# output.net
KiCad netlist of a schematic drawn in EAGLE
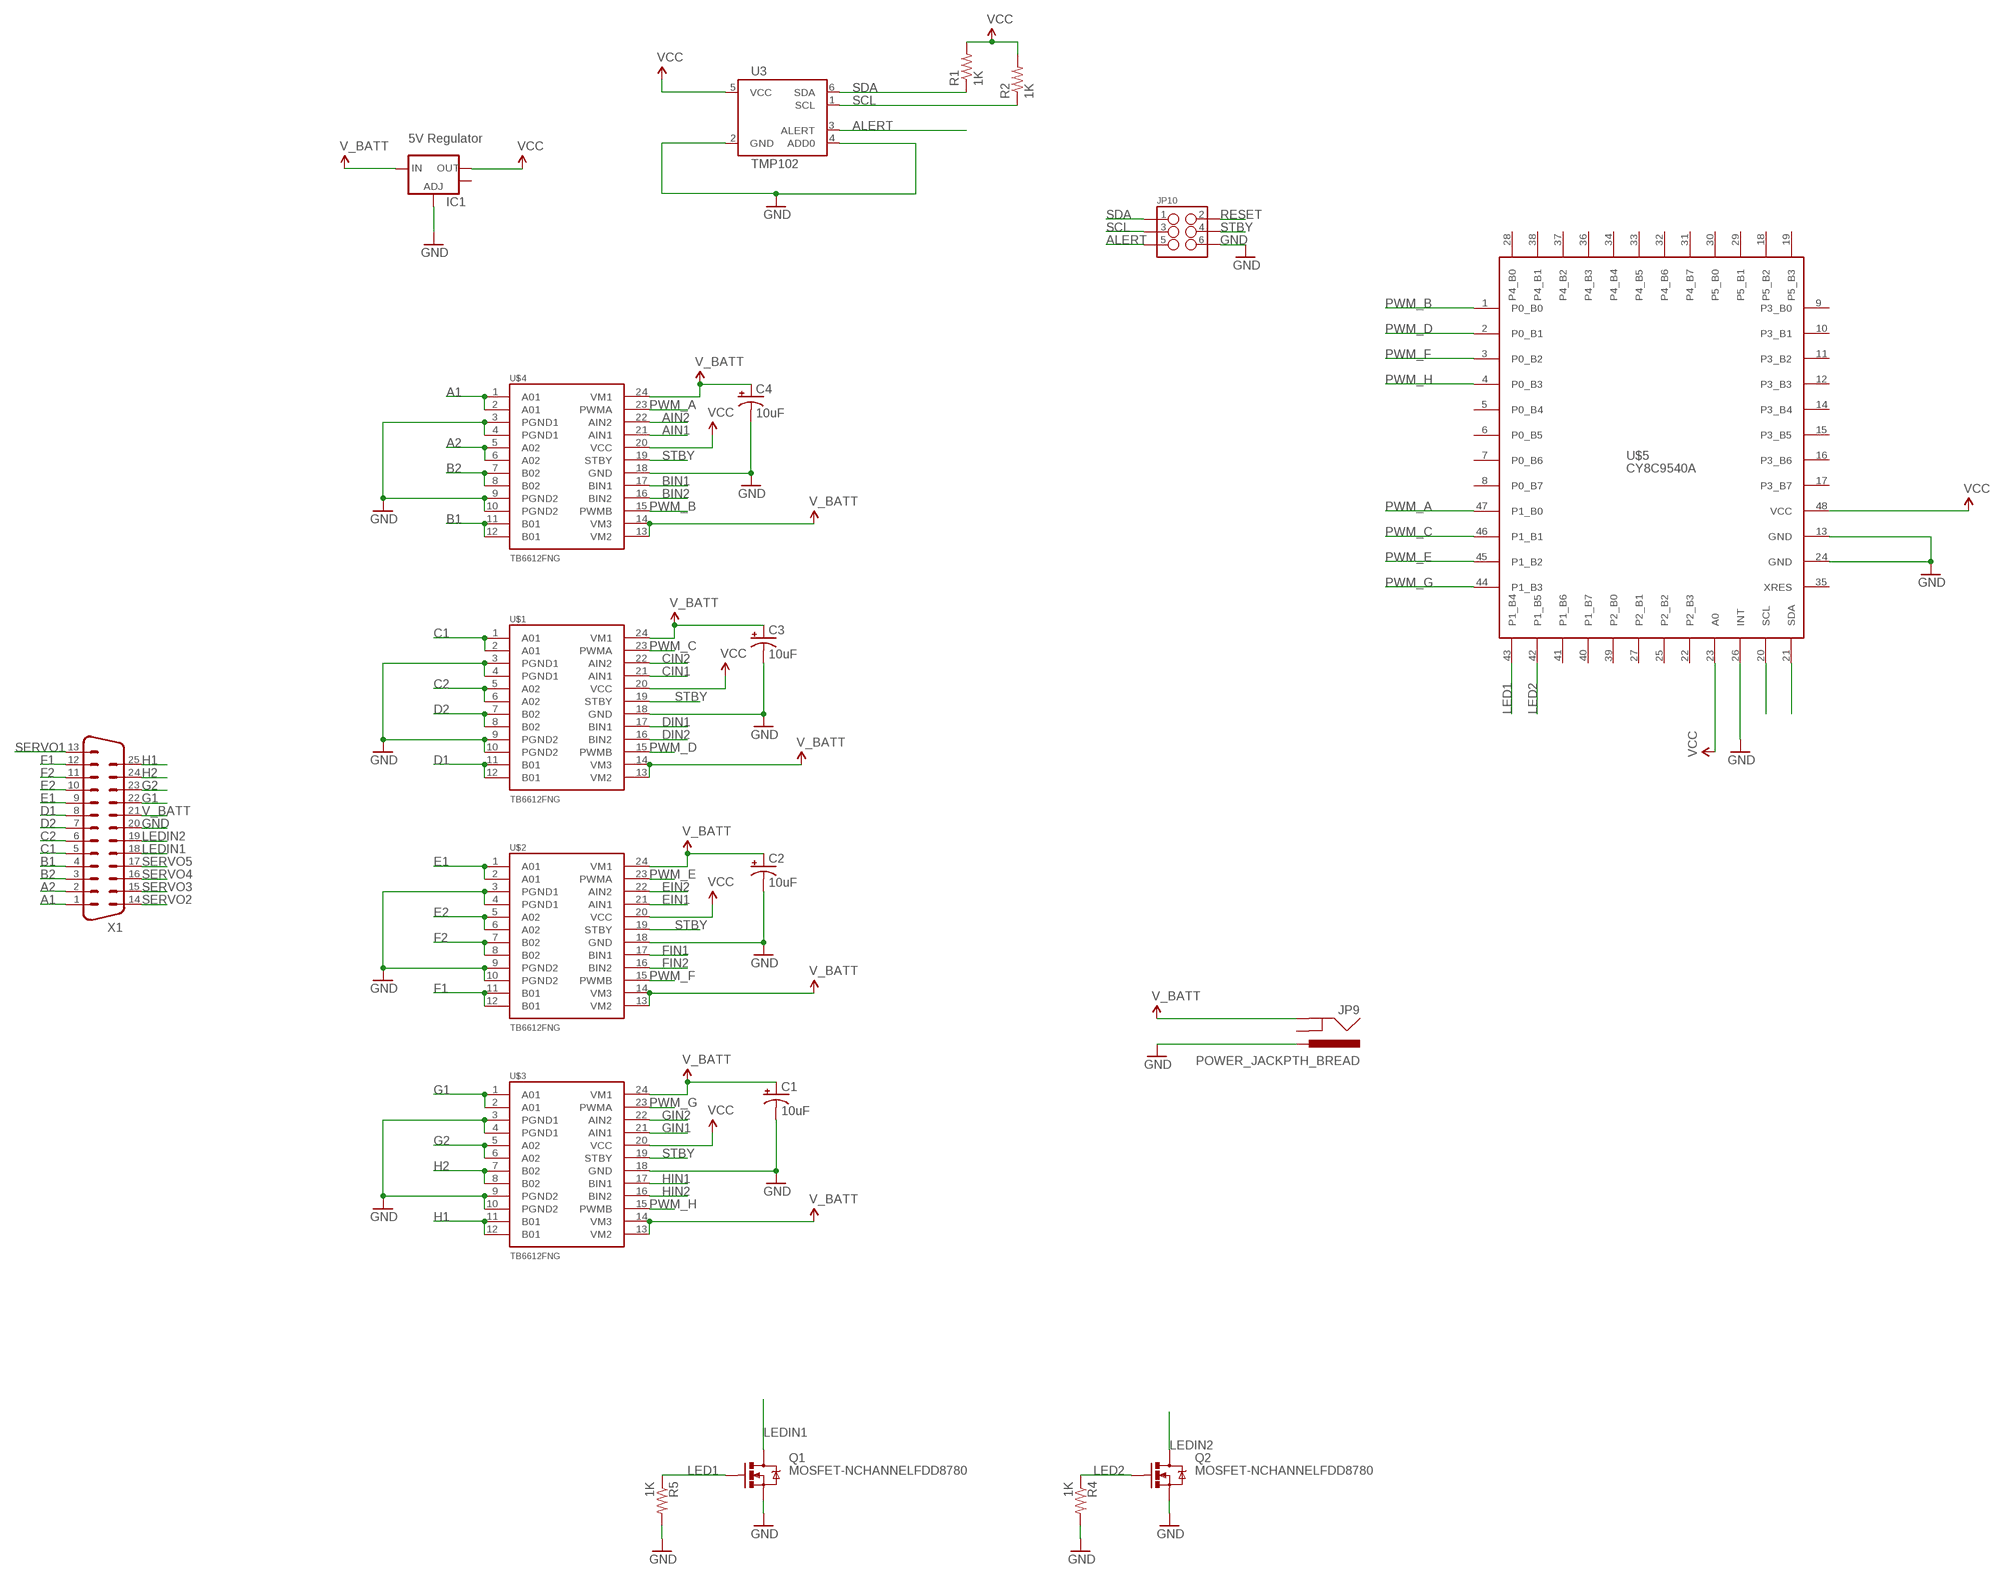
[diagram p0: schematic, sheet 1]

(export (version "E")
  (design (tool "Eeschema 10.0.6"))
  (components
    (comp (ref "C1")
      (value "10uF")
      (footprint "eagle-import:EIA3528")
      (libsource (lib "eagle-import") (part "10UF-20V-10%(TANT)"))
    )
    (comp (ref "C2")
      (value "10uF")
      (footprint "eagle-import:EIA3528")
      (libsource (lib "eagle-import") (part "10UF-20V-10%(TANT)"))
    )
    (comp (ref "C3")
      (value "10uF")
      (footprint "eagle-import:EIA3528")
      (libsource (lib "eagle-import") (part "10UF-20V-10%(TANT)"))
    )
    (comp (ref "C4")
      (value "10uF")
      (footprint "eagle-import:EIA3528")
      (libsource (lib "eagle-import") (part "10UF-20V-10%(TANT)"))
    )
    (comp (ref "IC1")
      (value "V_REG_LM1117SOT223")
      (footprint "eagle-import:SOT223")
      (libsource (lib "eagle-import") (part "V_REG_LM1117SOT223"))
    )
    (comp (ref "JP9")
      (value "POWER_JACKPTH_BREAD")
      (footprint "eagle-import:POWER_JACK_PTH_BREAD")
      (libsource (lib "eagle-import") (part "POWER_JACKPTH_BREAD"))
    )
    (comp (ref "JP10")
      (value "M03X2SHROUD")
      (footprint "eagle-import:2X3-SHROUDED")
      (libsource (lib "eagle-import") (part "M03X2SHROUD"))
    )
    (comp (ref "Q1")
      (value "MOSFET-NCHANNELFDD8780")
      (footprint "eagle-import:DPAK")
      (libsource (lib "eagle-import") (part "MOSFET-NCHANNELFDD8780"))
    )
    (comp (ref "Q2")
      (value "MOSFET-NCHANNELFDD8780")
      (footprint "eagle-import:DPAK")
      (libsource (lib "eagle-import") (part "MOSFET-NCHANNELFDD8780"))
    )
    (comp (ref "R1")
      (value "1K")
      (footprint "eagle-import:0603-RES")
      (libsource (lib "eagle-import") (part "1KOHM-1/10W-1%(0603)"))
    )
    (comp (ref "R2")
      (value "1K")
      (footprint "eagle-import:0603-RES")
      (libsource (lib "eagle-import") (part "1KOHM-1/10W-1%(0603)"))
    )
    (comp (ref "R4")
      (value "1K")
      (footprint "eagle-import:0603-RES")
      (libsource (lib "eagle-import") (part "1KOHM-1/10W-1%(0603)"))
    )
    (comp (ref "R5")
      (value "1K")
      (footprint "eagle-import:0603-RES")
      (libsource (lib "eagle-import") (part "1KOHM-1/10W-1%(0603)"))
    )
    (comp (ref "U$1")
      (value "TB6612FNG")
      (footprint "eagle-import:SSOP24")
      (libsource (lib "eagle-import") (part "TB6612FNG"))
    )
    (comp (ref "U$2")
      (value "TB6612FNG")
      (footprint "eagle-import:SSOP24")
      (libsource (lib "eagle-import") (part "TB6612FNG"))
    )
    (comp (ref "U$3")
      (value "TB6612FNG")
      (footprint "eagle-import:SSOP24")
      (libsource (lib "eagle-import") (part "TB6612FNG"))
    )
    (comp (ref "U$4")
      (value "TB6612FNG")
      (footprint "eagle-import:SSOP24")
      (libsource (lib "eagle-import") (part "TB6612FNG"))
    )
    (comp (ref "U$5")
      (value "CY8C9540A")
      (footprint "eagle-import:48-SSOP-CY")
      (libsource (lib "eagle-import") (part "CY8C9540A"))
    )
    (comp (ref "U3")
      (value "TMP102")
      (footprint "eagle-import:SOT563")
      (libsource (lib "eagle-import") (part "TMP102"))
    )
    (comp (ref "X1")
      (value "DB25D")
      (footprint "eagle-import:M25D")
      (libsource (lib "eagle-import") (part "DB25D"))
    )
  )
  (nets
    (net (code "1") (name "/A1") (class "Default")
      (node (ref "U$4") (pin "1") (pinfunction "A01_1") (pintype "bidirectional"))
      (node (ref "U$4") (pin "2") (pinfunction "A01_2") (pintype "bidirectional"))
      (node (ref "X1") (pin "1") (pinfunction "1_1") (pintype "passive"))
    )
    (net (code "2") (name "/A2") (class "Default")
      (node (ref "U$4") (pin "5") (pinfunction "A02_5") (pintype "bidirectional"))
      (node (ref "U$4") (pin "6") (pinfunction "A02_6") (pintype "bidirectional"))
      (node (ref "X1") (pin "2") (pinfunction "2_2") (pintype "passive"))
    )
    (net (code "3") (name "/AIN1") (class "Default")
      (node (ref "U$4") (pin "21") (pinfunction "AIN1_21") (pintype "bidirectional"))
    )
    (net (code "4") (name "/AIN2") (class "Default")
      (node (ref "U$4") (pin "22") (pinfunction "AIN2_22") (pintype "bidirectional"))
    )
    (net (code "5") (name "/ALERT") (class "Default")
      (node (ref "JP10") (pin "5") (pinfunction "5_5") (pintype "bidirectional"))
      (node (ref "U3") (pin "3") (pinfunction "ALERT_3") (pintype "bidirectional"))
    )
    (net (code "6") (name "/B1") (class "Default")
      (node (ref "U$4") (pin "11") (pinfunction "B01_11") (pintype "bidirectional"))
      (node (ref "U$4") (pin "12") (pinfunction "B01_12") (pintype "bidirectional"))
      (node (ref "X1") (pin "4") (pinfunction "4_4") (pintype "passive"))
    )
    (net (code "7") (name "/B2") (class "Default")
      (node (ref "U$4") (pin "7") (pinfunction "B02_7") (pintype "bidirectional"))
      (node (ref "U$4") (pin "8") (pinfunction "B02_8") (pintype "bidirectional"))
      (node (ref "X1") (pin "3") (pinfunction "3_3") (pintype "passive"))
    )
    (net (code "8") (name "/BIN1") (class "Default")
      (node (ref "U$4") (pin "17") (pinfunction "BIN1_17") (pintype "bidirectional"))
    )
    (net (code "9") (name "/BIN2") (class "Default")
      (node (ref "U$4") (pin "16") (pinfunction "BIN2_16") (pintype "bidirectional"))
    )
    (net (code "10") (name "/C1") (class "Default")
      (node (ref "U$1") (pin "1") (pinfunction "A01_1") (pintype "bidirectional"))
      (node (ref "U$1") (pin "2") (pinfunction "A01_2") (pintype "bidirectional"))
      (node (ref "X1") (pin "5") (pinfunction "5_5") (pintype "passive"))
    )
    (net (code "11") (name "/C2") (class "Default")
      (node (ref "U$1") (pin "5") (pinfunction "A02_5") (pintype "bidirectional"))
      (node (ref "U$1") (pin "6") (pinfunction "A02_6") (pintype "bidirectional"))
      (node (ref "X1") (pin "6") (pinfunction "6_6") (pintype "passive"))
    )
    (net (code "12") (name "/CIN1") (class "Default")
      (node (ref "U$1") (pin "21") (pinfunction "AIN1_21") (pintype "bidirectional"))
    )
    (net (code "13") (name "/CIN2") (class "Default")
      (node (ref "U$1") (pin "22") (pinfunction "AIN2_22") (pintype "bidirectional"))
    )
    (net (code "14") (name "/D1") (class "Default")
      (node (ref "U$1") (pin "11") (pinfunction "B01_11") (pintype "bidirectional"))
      (node (ref "U$1") (pin "12") (pinfunction "B01_12") (pintype "bidirectional"))
      (node (ref "X1") (pin "8") (pinfunction "8_8") (pintype "passive"))
    )
    (net (code "15") (name "/D2") (class "Default")
      (node (ref "U$1") (pin "7") (pinfunction "B02_7") (pintype "bidirectional"))
      (node (ref "U$1") (pin "8") (pinfunction "B02_8") (pintype "bidirectional"))
      (node (ref "X1") (pin "7") (pinfunction "7_7") (pintype "passive"))
    )
    (net (code "16") (name "/DIN1") (class "Default")
      (node (ref "U$1") (pin "17") (pinfunction "BIN1_17") (pintype "bidirectional"))
    )
    (net (code "17") (name "/DIN2") (class "Default")
      (node (ref "U$1") (pin "16") (pinfunction "BIN2_16") (pintype "bidirectional"))
    )
    (net (code "18") (name "/E1") (class "Default")
      (node (ref "U$2") (pin "1") (pinfunction "A01_1") (pintype "bidirectional"))
      (node (ref "U$2") (pin "2") (pinfunction "A01_2") (pintype "bidirectional"))
      (node (ref "X1") (pin "9") (pinfunction "9_9") (pintype "passive"))
    )
    (net (code "19") (name "/E2") (class "Default")
      (node (ref "U$2") (pin "5") (pinfunction "A02_5") (pintype "bidirectional"))
      (node (ref "U$2") (pin "6") (pinfunction "A02_6") (pintype "bidirectional"))
      (node (ref "X1") (pin "10") (pinfunction "10_10") (pintype "passive"))
    )
    (net (code "20") (name "/EIN1") (class "Default")
      (node (ref "U$2") (pin "21") (pinfunction "AIN1_21") (pintype "bidirectional"))
    )
    (net (code "21") (name "/EIN2") (class "Default")
      (node (ref "U$2") (pin "22") (pinfunction "AIN2_22") (pintype "bidirectional"))
    )
    (net (code "22") (name "/F1") (class "Default")
      (node (ref "U$2") (pin "11") (pinfunction "B01_11") (pintype "bidirectional"))
      (node (ref "U$2") (pin "12") (pinfunction "B01_12") (pintype "bidirectional"))
      (node (ref "X1") (pin "12") (pinfunction "12_12") (pintype "passive"))
    )
    (net (code "23") (name "/F2") (class "Default")
      (node (ref "U$2") (pin "7") (pinfunction "B02_7") (pintype "bidirectional"))
      (node (ref "U$2") (pin "8") (pinfunction "B02_8") (pintype "bidirectional"))
      (node (ref "X1") (pin "11") (pinfunction "11_11") (pintype "passive"))
    )
    (net (code "24") (name "/FIN1") (class "Default")
      (node (ref "U$2") (pin "17") (pinfunction "BIN1_17") (pintype "bidirectional"))
    )
    (net (code "25") (name "/FIN2") (class "Default")
      (node (ref "U$2") (pin "16") (pinfunction "BIN2_16") (pintype "bidirectional"))
    )
    (net (code "26") (name "/G1") (class "Default")
      (node (ref "U$3") (pin "1") (pinfunction "A01_1") (pintype "bidirectional"))
      (node (ref "U$3") (pin "2") (pinfunction "A01_2") (pintype "bidirectional"))
      (node (ref "X1") (pin "22") (pinfunction "22_22") (pintype "passive"))
    )
    (net (code "27") (name "/G2") (class "Default")
      (node (ref "U$3") (pin "5") (pinfunction "A02_5") (pintype "bidirectional"))
      (node (ref "U$3") (pin "6") (pinfunction "A02_6") (pintype "bidirectional"))
      (node (ref "X1") (pin "23") (pinfunction "23_23") (pintype "passive"))
    )
    (net (code "28") (name "/GIN1") (class "Default")
      (node (ref "U$3") (pin "21") (pinfunction "AIN1_21") (pintype "bidirectional"))
    )
    (net (code "29") (name "/GIN2") (class "Default")
      (node (ref "U$3") (pin "22") (pinfunction "AIN2_22") (pintype "bidirectional"))
    )
    (net (code "30") (name "/H1") (class "Default")
      (node (ref "U$3") (pin "11") (pinfunction "B01_11") (pintype "bidirectional"))
      (node (ref "U$3") (pin "12") (pinfunction "B01_12") (pintype "bidirectional"))
      (node (ref "X1") (pin "25") (pinfunction "25_25") (pintype "passive"))
    )
    (net (code "31") (name "/H2") (class "Default")
      (node (ref "U$3") (pin "7") (pinfunction "B02_7") (pintype "bidirectional"))
      (node (ref "U$3") (pin "8") (pinfunction "B02_8") (pintype "bidirectional"))
      (node (ref "X1") (pin "24") (pinfunction "24_24") (pintype "passive"))
    )
    (net (code "32") (name "/HIN1") (class "Default")
      (node (ref "U$3") (pin "17") (pinfunction "BIN1_17") (pintype "bidirectional"))
    )
    (net (code "33") (name "/HIN2") (class "Default")
      (node (ref "U$3") (pin "16") (pinfunction "BIN2_16") (pintype "bidirectional"))
    )
    (net (code "34") (name "/LED1") (class "Default")
      (node (ref "Q1") (pin "1") (pinfunction "G_1") (pintype "passive"))
      (node (ref "R5") (pin "1") (pinfunction "1_1") (pintype "passive"))
      (node (ref "U$5") (pin "43") (pinfunction "P1_B4_43") (pintype "bidirectional"))
    )
    (net (code "35") (name "/LED2") (class "Default")
      (node (ref "Q2") (pin "1") (pinfunction "G_1") (pintype "passive"))
      (node (ref "R4") (pin "1") (pinfunction "1_1") (pintype "passive"))
      (node (ref "U$5") (pin "42") (pinfunction "P1_B5_42") (pintype "bidirectional"))
    )
    (net (code "36") (name "/LEDIN1") (class "Default")
      (node (ref "Q1") (pin "4") (pinfunction "D_4") (pintype "passive"))
      (node (ref "X1") (pin "18") (pinfunction "18_18") (pintype "passive"))
    )
    (net (code "37") (name "/LEDIN2") (class "Default")
      (node (ref "Q2") (pin "4") (pinfunction "D_4") (pintype "passive"))
      (node (ref "X1") (pin "19") (pinfunction "19_19") (pintype "passive"))
    )
    (net (code "38") (name "/PWM_A") (class "Default")
      (node (ref "U$4") (pin "23") (pinfunction "PWMA_23") (pintype "bidirectional"))
      (node (ref "U$5") (pin "47") (pinfunction "P1_B0_47") (pintype "bidirectional"))
    )
    (net (code "39") (name "/PWM_B") (class "Default")
      (node (ref "U$4") (pin "15") (pinfunction "PWMB_15") (pintype "bidirectional"))
      (node (ref "U$5") (pin "1") (pinfunction "P0_B0_1") (pintype "bidirectional"))
    )
    (net (code "40") (name "/PWM_C") (class "Default")
      (node (ref "U$1") (pin "23") (pinfunction "PWMA_23") (pintype "bidirectional"))
      (node (ref "U$5") (pin "46") (pinfunction "P1_B1_46") (pintype "bidirectional"))
    )
    (net (code "41") (name "/PWM_D") (class "Default")
      (node (ref "U$1") (pin "15") (pinfunction "PWMB_15") (pintype "bidirectional"))
      (node (ref "U$5") (pin "2") (pinfunction "P0_B1_2") (pintype "bidirectional"))
    )
    (net (code "42") (name "/PWM_E") (class "Default")
      (node (ref "U$2") (pin "23") (pinfunction "PWMA_23") (pintype "bidirectional"))
      (node (ref "U$5") (pin "45") (pinfunction "P1_B2_45") (pintype "bidirectional"))
    )
    (net (code "43") (name "/PWM_F") (class "Default")
      (node (ref "U$2") (pin "15") (pinfunction "PWMB_15") (pintype "bidirectional"))
      (node (ref "U$5") (pin "3") (pinfunction "P0_B2_3") (pintype "bidirectional"))
    )
    (net (code "44") (name "/PWM_G") (class "Default")
      (node (ref "U$3") (pin "23") (pinfunction "PWMA_23") (pintype "bidirectional"))
      (node (ref "U$5") (pin "44") (pinfunction "P1_B3_44") (pintype "bidirectional"))
    )
    (net (code "45") (name "/PWM_H") (class "Default")
      (node (ref "U$3") (pin "15") (pinfunction "PWMB_15") (pintype "bidirectional"))
      (node (ref "U$5") (pin "4") (pinfunction "P0_B3_4") (pintype "bidirectional"))
    )
    (net (code "46") (name "/RESET") (class "Default")
      (node (ref "JP10") (pin "2") (pinfunction "2_2") (pintype "bidirectional"))
    )
    (net (code "47") (name "/SCL") (class "Default")
      (node (ref "JP10") (pin "3") (pinfunction "3_3") (pintype "bidirectional"))
      (node (ref "R2") (pin "1") (pinfunction "1_1") (pintype "passive"))
      (node (ref "U$5") (pin "20") (pinfunction "SCL_20") (pintype "bidirectional"))
      (node (ref "U3") (pin "1") (pinfunction "SCL_1") (pintype "bidirectional"))
    )
    (net (code "48") (name "/SDA") (class "Default")
      (node (ref "JP10") (pin "1") (pinfunction "1_1") (pintype "bidirectional"))
      (node (ref "R1") (pin "1") (pinfunction "1_1") (pintype "passive"))
      (node (ref "U$5") (pin "21") (pinfunction "SDA_21") (pintype "bidirectional"))
      (node (ref "U3") (pin "6") (pinfunction "SDA_6") (pintype "bidirectional"))
    )
    (net (code "49") (name "/SERVO1") (class "Default")
      (node (ref "X1") (pin "13") (pinfunction "13_13") (pintype "passive"))
    )
    (net (code "50") (name "/SERVO2") (class "Default")
      (node (ref "X1") (pin "14") (pinfunction "14_14") (pintype "passive"))
    )
    (net (code "51") (name "/SERVO3") (class "Default")
      (node (ref "X1") (pin "15") (pinfunction "15_15") (pintype "passive"))
    )
    (net (code "52") (name "/SERVO4") (class "Default")
      (node (ref "X1") (pin "16") (pinfunction "16_16") (pintype "passive"))
    )
    (net (code "53") (name "/SERVO5") (class "Default")
      (node (ref "X1") (pin "17") (pinfunction "17_17") (pintype "passive"))
    )
    (net (code "54") (name "/STBY") (class "Default")
      (node (ref "JP10") (pin "4") (pinfunction "4_4") (pintype "bidirectional"))
      (node (ref "U$1") (pin "19") (pinfunction "STBY_19") (pintype "bidirectional"))
      (node (ref "U$2") (pin "19") (pinfunction "STBY_19") (pintype "bidirectional"))
      (node (ref "U$3") (pin "19") (pinfunction "STBY_19") (pintype "bidirectional"))
      (node (ref "U$4") (pin "19") (pinfunction "STBY_19") (pintype "bidirectional"))
    )
    (net (code "55") (name "GND") (class "Default")
      (node (ref "C1") (pin "C") (pinfunction "-_C") (pintype "passive"))
      (node (ref "C2") (pin "C") (pinfunction "-_C") (pintype "passive"))
      (node (ref "C3") (pin "C") (pinfunction "-_C") (pintype "passive"))
      (node (ref "C4") (pin "C") (pinfunction "-_C") (pintype "passive"))
      (node (ref "IC1") (pin "1") (pinfunction "ADJ_1") (pintype "input"))
      (node (ref "JP10") (pin "6") (pinfunction "6_6") (pintype "bidirectional"))
      (node (ref "JP9") (pin "PWR") (pinfunction "PWR_PWR") (pintype "bidirectional"))
      (node (ref "Q1") (pin "3") (pinfunction "S_3") (pintype "passive"))
      (node (ref "Q2") (pin "3") (pinfunction "S_3") (pintype "passive"))
      (node (ref "R4") (pin "2") (pinfunction "2_2") (pintype "passive"))
      (node (ref "R5") (pin "2") (pinfunction "2_2") (pintype "passive"))
      (node (ref "U$1") (pin "10") (pinfunction "PGND2_10") (pintype "bidirectional"))
      (node (ref "U$1") (pin "18") (pinfunction "GND_18") (pintype "bidirectional"))
      (node (ref "U$1") (pin "3") (pinfunction "PGND1_3") (pintype "bidirectional"))
      (node (ref "U$1") (pin "4") (pinfunction "PGND1_4") (pintype "bidirectional"))
      (node (ref "U$1") (pin "9") (pinfunction "PGND2_9") (pintype "bidirectional"))
      (node (ref "U$2") (pin "10") (pinfunction "PGND2_10") (pintype "bidirectional"))
      (node (ref "U$2") (pin "18") (pinfunction "GND_18") (pintype "bidirectional"))
      (node (ref "U$2") (pin "3") (pinfunction "PGND1_3") (pintype "bidirectional"))
      (node (ref "U$2") (pin "4") (pinfunction "PGND1_4") (pintype "bidirectional"))
      (node (ref "U$2") (pin "9") (pinfunction "PGND2_9") (pintype "bidirectional"))
      (node (ref "U$3") (pin "10") (pinfunction "PGND2_10") (pintype "bidirectional"))
      (node (ref "U$3") (pin "18") (pinfunction "GND_18") (pintype "bidirectional"))
      (node (ref "U$3") (pin "3") (pinfunction "PGND1_3") (pintype "bidirectional"))
      (node (ref "U$3") (pin "4") (pinfunction "PGND1_4") (pintype "bidirectional"))
      (node (ref "U$3") (pin "9") (pinfunction "PGND2_9") (pintype "bidirectional"))
      (node (ref "U$4") (pin "10") (pinfunction "PGND2_10") (pintype "bidirectional"))
      (node (ref "U$4") (pin "18") (pinfunction "GND_18") (pintype "bidirectional"))
      (node (ref "U$4") (pin "3") (pinfunction "PGND1_3") (pintype "bidirectional"))
      (node (ref "U$4") (pin "4") (pinfunction "PGND1_4") (pintype "bidirectional"))
      (node (ref "U$4") (pin "9") (pinfunction "PGND2_9") (pintype "bidirectional"))
      (node (ref "U$5") (pin "13") (pinfunction "GND_13") (pintype "bidirectional"))
      (node (ref "U$5") (pin "24") (pinfunction "GND_24") (pintype "bidirectional"))
      (node (ref "U$5") (pin "26") (pinfunction "INT_26") (pintype "bidirectional"))
      (node (ref "U3") (pin "2") (pinfunction "GND_2") (pintype "bidirectional"))
      (node (ref "U3") (pin "4") (pinfunction "ADD0_4") (pintype "bidirectional"))
      (node (ref "X1") (pin "20") (pinfunction "20_20") (pintype "passive"))
    )
    (net (code "56") (name "VCC") (class "Default")
      (node (ref "IC1") (pin "2") (pinfunction "OUT_2") (pintype "output"))
      (node (ref "R1") (pin "2") (pinfunction "2_2") (pintype "passive"))
      (node (ref "R2") (pin "2") (pinfunction "2_2") (pintype "passive"))
      (node (ref "U$1") (pin "20") (pinfunction "VCC_20") (pintype "bidirectional"))
      (node (ref "U$2") (pin "20") (pinfunction "VCC_20") (pintype "bidirectional"))
      (node (ref "U$3") (pin "20") (pinfunction "VCC_20") (pintype "bidirectional"))
      (node (ref "U$4") (pin "20") (pinfunction "VCC_20") (pintype "bidirectional"))
      (node (ref "U$5") (pin "23") (pinfunction "A0_23") (pintype "bidirectional"))
      (node (ref "U$5") (pin "48") (pinfunction "VCC_48") (pintype "bidirectional"))
      (node (ref "U3") (pin "5") (pinfunction "VCC_5") (pintype "bidirectional"))
    )
    (net (code "57") (name "V_BATT") (class "Default")
      (node (ref "C1") (pin "A") (pinfunction "+_A") (pintype "passive"))
      (node (ref "C2") (pin "A") (pinfunction "+_A") (pintype "passive"))
      (node (ref "C3") (pin "A") (pinfunction "+_A") (pintype "passive"))
      (node (ref "C4") (pin "A") (pinfunction "+_A") (pintype "passive"))
      (node (ref "IC1") (pin "3") (pinfunction "IN_3") (pintype "input"))
      (node (ref "JP9") (pin "GND") (pinfunction "GND_GND") (pintype "bidirectional"))
      (node (ref "U$1") (pin "13") (pinfunction "VM2_13") (pintype "bidirectional"))
      (node (ref "U$1") (pin "14") (pinfunction "VM3_14") (pintype "bidirectional"))
      (node (ref "U$1") (pin "24") (pinfunction "VM1_24") (pintype "bidirectional"))
      (node (ref "U$2") (pin "13") (pinfunction "VM2_13") (pintype "bidirectional"))
      (node (ref "U$2") (pin "14") (pinfunction "VM3_14") (pintype "bidirectional"))
      (node (ref "U$2") (pin "24") (pinfunction "VM1_24") (pintype "bidirectional"))
      (node (ref "U$3") (pin "13") (pinfunction "VM2_13") (pintype "bidirectional"))
      (node (ref "U$3") (pin "14") (pinfunction "VM3_14") (pintype "bidirectional"))
      (node (ref "U$3") (pin "24") (pinfunction "VM1_24") (pintype "bidirectional"))
      (node (ref "U$4") (pin "13") (pinfunction "VM2_13") (pintype "bidirectional"))
      (node (ref "U$4") (pin "14") (pinfunction "VM3_14") (pintype "bidirectional"))
      (node (ref "U$4") (pin "24") (pinfunction "VM1_24") (pintype "bidirectional"))
      (node (ref "X1") (pin "21") (pinfunction "21_21") (pintype "passive"))
    )
    (net (code "58") (name "unconnected-(IC1-OUT-Pad4)") (class "Default")
      (node (ref "IC1") (pin "4") (pinfunction "OUT_4") (pintype "output"))
    )
    (net (code "59") (name "unconnected-(JP9-PadGNDBREAK)") (class "Default")
      (node (ref "JP9") (pin "GNDBREAK") (pinfunction "GNDBREAK_GNDBREAK") (pintype "bidirectional"))
    )
    (net (code "60") (name "unconnected-(U$5-P0_B4-Pad5)") (class "Default")
      (node (ref "U$5") (pin "5") (pinfunction "P0_B4_5") (pintype "bidirectional"))
    )
    (net (code "61") (name "unconnected-(U$5-P0_B5-Pad6)") (class "Default")
      (node (ref "U$5") (pin "6") (pinfunction "P0_B5_6") (pintype "bidirectional"))
    )
    (net (code "62") (name "unconnected-(U$5-P0_B6-Pad7)") (class "Default")
      (node (ref "U$5") (pin "7") (pinfunction "P0_B6_7") (pintype "bidirectional"))
    )
    (net (code "63") (name "unconnected-(U$5-P0_B7-Pad8)") (class "Default")
      (node (ref "U$5") (pin "8") (pinfunction "P0_B7_8") (pintype "bidirectional"))
    )
    (net (code "64") (name "unconnected-(U$5-P1_B6-Pad41)") (class "Default")
      (node (ref "U$5") (pin "41") (pinfunction "P1_B6_41") (pintype "bidirectional"))
    )
    (net (code "65") (name "unconnected-(U$5-P1_B7-Pad40)") (class "Default")
      (node (ref "U$5") (pin "40") (pinfunction "P1_B7_40") (pintype "bidirectional"))
    )
    (net (code "66") (name "unconnected-(U$5-P2_B0-Pad39)") (class "Default")
      (node (ref "U$5") (pin "39") (pinfunction "P2_B0_39") (pintype "bidirectional"))
    )
    (net (code "67") (name "unconnected-(U$5-P2_B1-Pad27)") (class "Default")
      (node (ref "U$5") (pin "27") (pinfunction "P2_B1_27") (pintype "bidirectional"))
    )
    (net (code "68") (name "unconnected-(U$5-P2_B2-Pad25)") (class "Default")
      (node (ref "U$5") (pin "25") (pinfunction "P2_B2_25") (pintype "bidirectional"))
    )
    (net (code "69") (name "unconnected-(U$5-P2_B3-Pad22)") (class "Default")
      (node (ref "U$5") (pin "22") (pinfunction "P2_B3_22") (pintype "bidirectional"))
    )
    (net (code "70") (name "unconnected-(U$5-P3_B0-Pad9)") (class "Default")
      (node (ref "U$5") (pin "9") (pinfunction "P3_B0_9") (pintype "bidirectional"))
    )
    (net (code "71") (name "unconnected-(U$5-P3_B1-Pad10)") (class "Default")
      (node (ref "U$5") (pin "10") (pinfunction "P3_B1_10") (pintype "bidirectional"))
    )
    (net (code "72") (name "unconnected-(U$5-P3_B2-Pad11)") (class "Default")
      (node (ref "U$5") (pin "11") (pinfunction "P3_B2_11") (pintype "bidirectional"))
    )
    (net (code "73") (name "unconnected-(U$5-P3_B3-Pad12)") (class "Default")
      (node (ref "U$5") (pin "12") (pinfunction "P3_B3_12") (pintype "bidirectional"))
    )
    (net (code "74") (name "unconnected-(U$5-P3_B4-Pad14)") (class "Default")
      (node (ref "U$5") (pin "14") (pinfunction "P3_B4_14") (pintype "bidirectional"))
    )
    (net (code "75") (name "unconnected-(U$5-P3_B5-Pad15)") (class "Default")
      (node (ref "U$5") (pin "15") (pinfunction "P3_B5_15") (pintype "bidirectional"))
    )
    (net (code "76") (name "unconnected-(U$5-P3_B6-Pad16)") (class "Default")
      (node (ref "U$5") (pin "16") (pinfunction "P3_B6_16") (pintype "bidirectional"))
    )
    (net (code "77") (name "unconnected-(U$5-P3_B7-Pad17)") (class "Default")
      (node (ref "U$5") (pin "17") (pinfunction "P3_B7_17") (pintype "bidirectional"))
    )
    (net (code "78") (name "unconnected-(U$5-P4_B0-Pad28)") (class "Default")
      (node (ref "U$5") (pin "28") (pinfunction "P4_B0_28") (pintype "bidirectional"))
    )
    (net (code "79") (name "unconnected-(U$5-P4_B1-Pad38)") (class "Default")
      (node (ref "U$5") (pin "38") (pinfunction "P4_B1_38") (pintype "bidirectional"))
    )
    (net (code "80") (name "unconnected-(U$5-P4_B2-Pad37)") (class "Default")
      (node (ref "U$5") (pin "37") (pinfunction "P4_B2_37") (pintype "bidirectional"))
    )
    (net (code "81") (name "unconnected-(U$5-P4_B3-Pad36)") (class "Default")
      (node (ref "U$5") (pin "36") (pinfunction "P4_B3_36") (pintype "bidirectional"))
    )
    (net (code "82") (name "unconnected-(U$5-P4_B4-Pad34)") (class "Default")
      (node (ref "U$5") (pin "34") (pinfunction "P4_B4_34") (pintype "bidirectional"))
    )
    (net (code "83") (name "unconnected-(U$5-P4_B5-Pad33)") (class "Default")
      (node (ref "U$5") (pin "33") (pinfunction "P4_B5_33") (pintype "bidirectional"))
    )
    (net (code "84") (name "unconnected-(U$5-P4_B6-Pad32)") (class "Default")
      (node (ref "U$5") (pin "32") (pinfunction "P4_B6_32") (pintype "bidirectional"))
    )
    (net (code "85") (name "unconnected-(U$5-P4_B7-Pad31)") (class "Default")
      (node (ref "U$5") (pin "31") (pinfunction "P4_B7_31") (pintype "bidirectional"))
    )
    (net (code "86") (name "unconnected-(U$5-P5_B0-Pad30)") (class "Default")
      (node (ref "U$5") (pin "30") (pinfunction "P5_B0_30") (pintype "bidirectional"))
    )
    (net (code "87") (name "unconnected-(U$5-P5_B1-Pad29)") (class "Default")
      (node (ref "U$5") (pin "29") (pinfunction "P5_B1_29") (pintype "bidirectional"))
    )
    (net (code "88") (name "unconnected-(U$5-P5_B2-Pad18)") (class "Default")
      (node (ref "U$5") (pin "18") (pinfunction "P5_B2_18") (pintype "bidirectional"))
    )
    (net (code "89") (name "unconnected-(U$5-P5_B3-Pad19)") (class "Default")
      (node (ref "U$5") (pin "19") (pinfunction "P5_B3_19") (pintype "bidirectional"))
    )
    (net (code "90") (name "unconnected-(U$5-XRES-Pad35)") (class "Default")
      (node (ref "U$5") (pin "35") (pinfunction "XRES_35") (pintype "bidirectional"))
    )
  )
)
